# Power_3_3V.net
KiCad netlist of a schematic drawn in Altium Designer
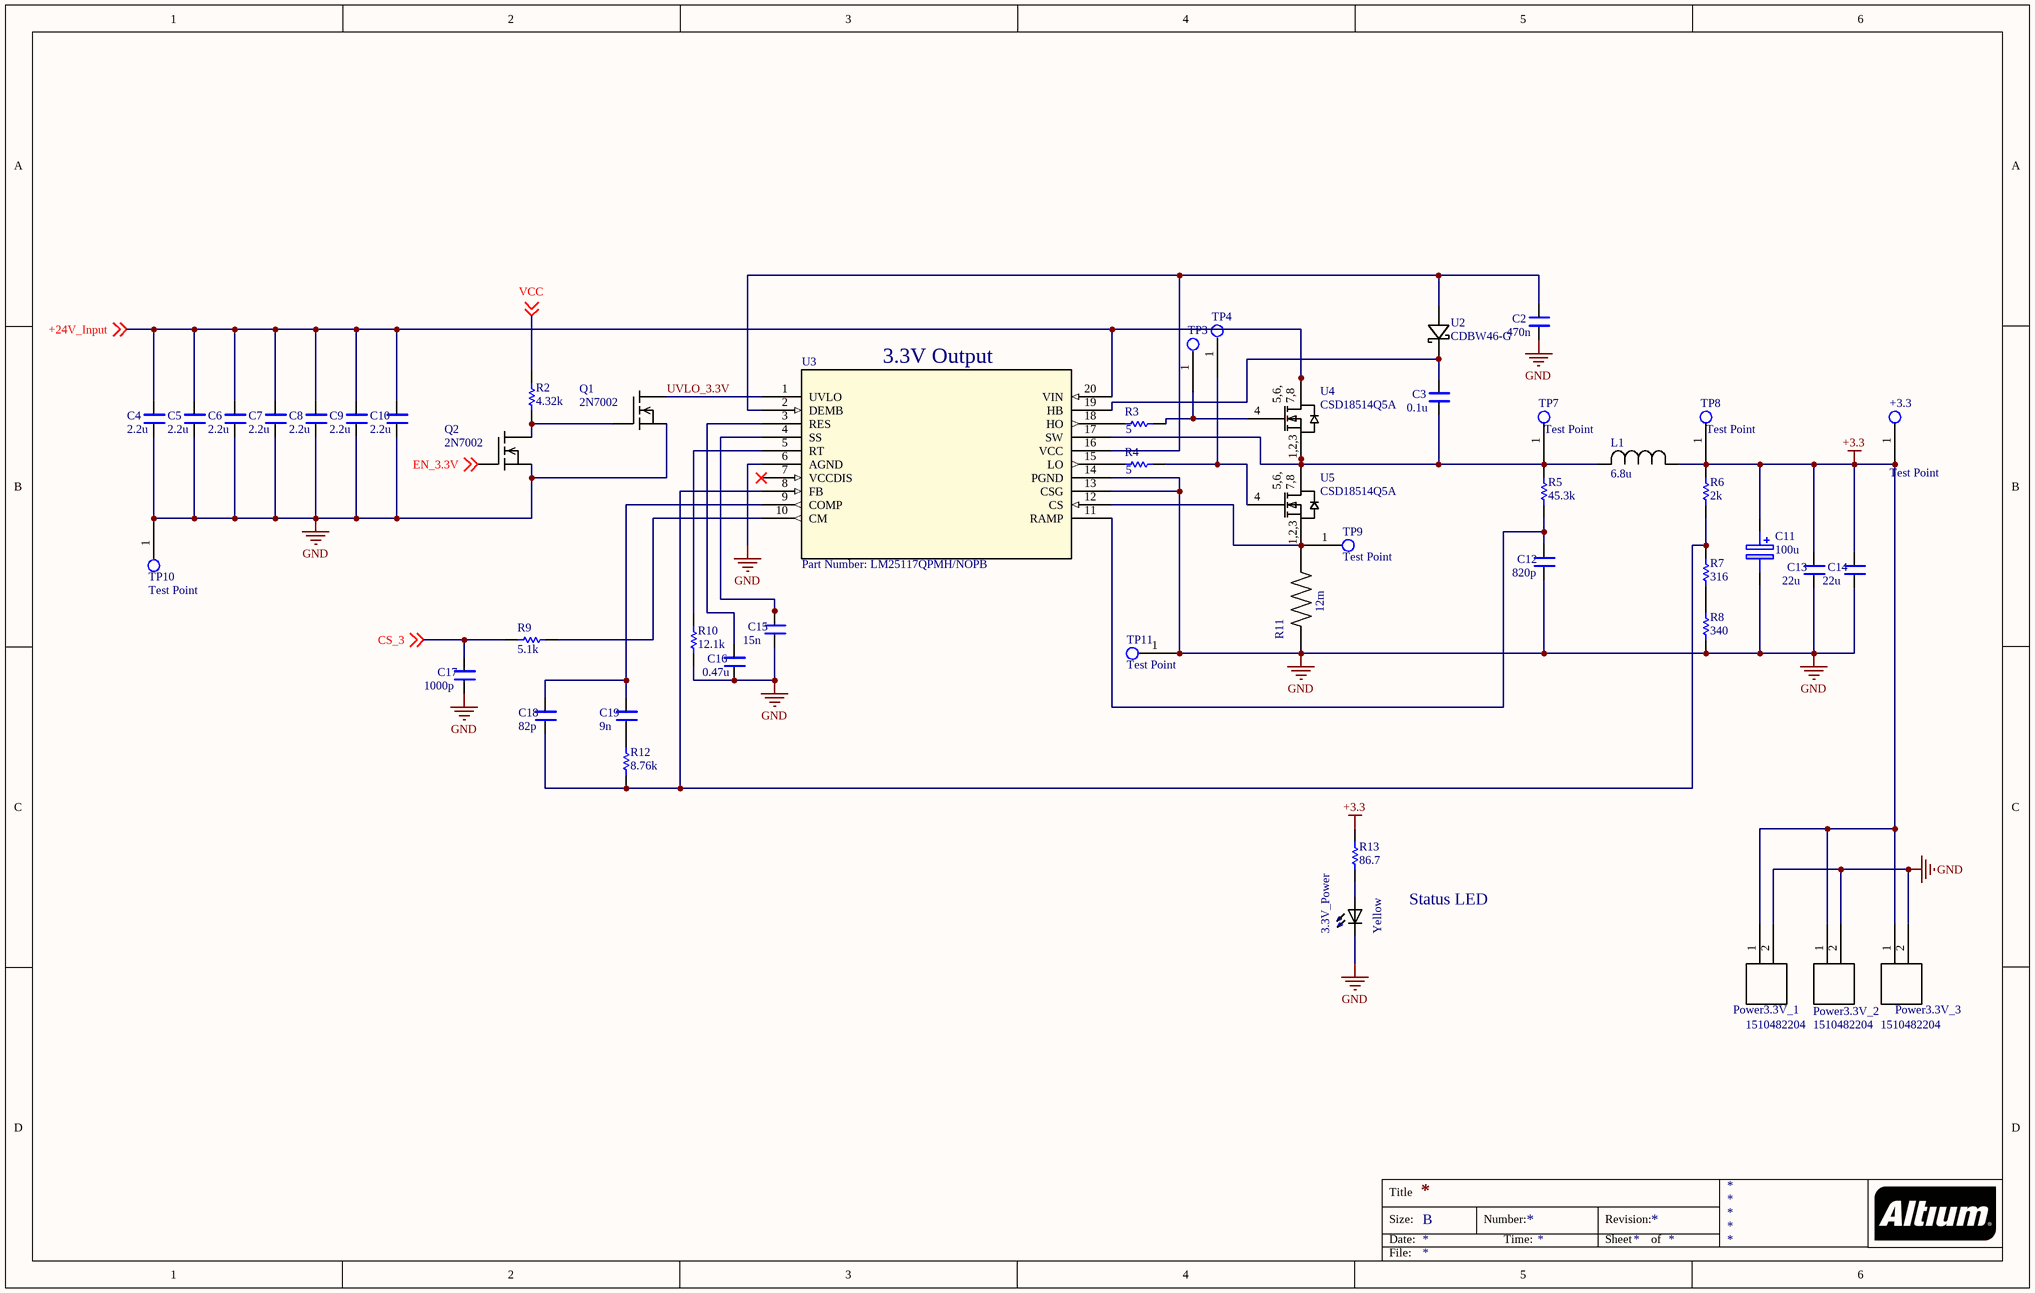
[diagram p0: Power_3.3V.SchDoc]

(export (version "E")
  (design (tool "Eeschema 10.0.6"))
  (components
    (comp (ref "+3.3")
      (value "Test Point")
      (footprint "Test Point Through-hole")
      (libsource (lib "Test Points") (part "Test Point"))
    )
    (comp (ref "3.3V_Power")
      (value "Yellow")
      (footprint "*DIOC200X125X110_LTST-C171KSKT(Primary)")
      (description "Yellow 2 x 1.25 x 0.8 mm 130Â° Water Clear 50 mcd 2 V LED SMT")
      (fields (field (name "MP") "LTST-C171KSKT") (field (name "DIGI-KEY_PART_NUMBER") "160-1428-1-ND"))
      (libsource (lib "LTST-C171KSKT") (part "LTST-C171KSKT"))
    )
    (comp (ref "C2")
      (value "470n")
      (footprint "*CAPC2012X88N")
      (description "100pF Â±5% 250V Ceramic Capacitor C0G, NP0 0805 _2012 Metric_")
      (fields (field (name "MF") "KEMET") (field (name "DIGI-KEY_PART_NUMBER") "399-15000-1-ND"))
      (libsource (lib "C0805C101JAGAC7800") (part "C0805C101JAGAC7800"))
    )
    (comp (ref "C3")
      (value "0.1u")
      (footprint "*CAPC2012X88N")
      (description "100pF Â±5% 250V Ceramic Capacitor C0G, NP0 0805 _2012 Metric_")
      (fields (field (name "MF") "KEMET") (field (name "DIGI-KEY_PART_NUMBER") "399-15000-1-ND"))
      (libsource (lib "C0805C101JAGAC7800") (part "C0805C101JAGAC7800"))
    )
    (comp (ref "C4")
      (value "2.2u")
      (footprint "*CAPC2012X88N")
      (description "100pF Â±5% 250V Ceramic Capacitor C0G, NP0 0805 _2012 Metric_")
      (fields (field (name "MF") "KEMET") (field (name "DIGI-KEY_PART_NUMBER") "399-15000-1-ND"))
      (libsource (lib "C0805C101JAGAC7800") (part "C0805C101JAGAC7800"))
    )
    (comp (ref "C5")
      (value "2.2u")
      (footprint "*CAPC2012X88N")
      (description "100pF Â±5% 250V Ceramic Capacitor C0G, NP0 0805 _2012 Metric_")
      (fields (field (name "MF") "KEMET") (field (name "DIGI-KEY_PART_NUMBER") "399-15000-1-ND"))
      (libsource (lib "C0805C101JAGAC7800") (part "C0805C101JAGAC7800"))
    )
    (comp (ref "C6")
      (value "2.2u")
      (footprint "*CAPC2012X88N")
      (description "100pF Â±5% 250V Ceramic Capacitor C0G, NP0 0805 _2012 Metric_")
      (fields (field (name "MF") "KEMET") (field (name "DIGI-KEY_PART_NUMBER") "399-15000-1-ND"))
      (libsource (lib "C0805C101JAGAC7800") (part "C0805C101JAGAC7800"))
    )
    (comp (ref "C7")
      (value "2.2u")
      (footprint "*CAPC2012X88N")
      (description "100pF Â±5% 250V Ceramic Capacitor C0G, NP0 0805 _2012 Metric_")
      (fields (field (name "MF") "KEMET") (field (name "DIGI-KEY_PART_NUMBER") "399-15000-1-ND"))
      (libsource (lib "C0805C101JAGAC7800") (part "C0805C101JAGAC7800"))
    )
    (comp (ref "C8")
      (value "2.2u")
      (footprint "*CAPC2012X88N")
      (description "100pF Â±5% 250V Ceramic Capacitor C0G, NP0 0805 _2012 Metric_")
      (fields (field (name "MF") "KEMET") (field (name "DIGI-KEY_PART_NUMBER") "399-15000-1-ND"))
      (libsource (lib "C0805C101JAGAC7800") (part "C0805C101JAGAC7800"))
    )
    (comp (ref "C9")
      (value "2.2u")
      (footprint "*CAPC2012X88N")
      (description "100pF Â±5% 250V Ceramic Capacitor C0G, NP0 0805 _2012 Metric_")
      (fields (field (name "MF") "KEMET") (field (name "DIGI-KEY_PART_NUMBER") "399-15000-1-ND"))
      (libsource (lib "C0805C101JAGAC7800") (part "C0805C101JAGAC7800"))
    )
    (comp (ref "C10")
      (value "2.2u")
      (footprint "*CAPC2012X88N")
      (description "100pF Â±5% 250V Ceramic Capacitor C0G, NP0 0805 _2012 Metric_")
      (fields (field (name "MF") "KEMET") (field (name "DIGI-KEY_PART_NUMBER") "399-15000-1-ND"))
      (libsource (lib "C0805C101JAGAC7800") (part "C0805C101JAGAC7800"))
    )
    (comp (ref "C11")
      (value "100u")
      (footprint "CAPPRD500W65D1000H1800")
      (fields
        (field (name "MANUFACTURER_PART_NUMBER") "EEUFC1V331")
        (field (name "RS PART NUMBER") "1081337")
      )
      (libsource (lib "Power Distribution") (part "EEUFC1V331"))
    )
    (comp (ref "C12")
      (value "820p")
      (footprint "*CAPC2012X88N")
      (description "100pF Â±5% 250V Ceramic Capacitor C0G, NP0 0805 _2012 Metric_")
      (fields (field (name "MF") "KEMET") (field (name "DIGI-KEY_PART_NUMBER") "399-15000-1-ND"))
      (libsource (lib "C0805C101JAGAC7800") (part "C0805C101JAGAC7800"))
    )
    (comp (ref "C13")
      (value "22u")
      (footprint "*CAPC2012X88N")
      (description "100pF Â±5% 250V Ceramic Capacitor C0G, NP0 0805 _2012 Metric_")
      (fields (field (name "MF") "KEMET") (field (name "DIGI-KEY_PART_NUMBER") "399-15000-1-ND"))
      (libsource (lib "C0805C101JAGAC7800") (part "C0805C101JAGAC7800"))
    )
    (comp (ref "C14")
      (value "22u")
      (footprint "*CAPC2012X88N")
      (description "100pF Â±5% 250V Ceramic Capacitor C0G, NP0 0805 _2012 Metric_")
      (fields (field (name "MF") "KEMET") (field (name "DIGI-KEY_PART_NUMBER") "399-15000-1-ND"))
      (libsource (lib "C0805C101JAGAC7800") (part "C0805C101JAGAC7800"))
    )
    (comp (ref "C15")
      (value "15n")
      (footprint "*CAPC2012X88N")
      (description "100pF Â±5% 250V Ceramic Capacitor C0G, NP0 0805 _2012 Metric_")
      (fields (field (name "MF") "KEMET") (field (name "DIGI-KEY_PART_NUMBER") "399-15000-1-ND"))
      (libsource (lib "C0805C101JAGAC7800") (part "C0805C101JAGAC7800"))
    )
    (comp (ref "C16")
      (value "0.47u")
      (footprint "*CAPC2012X88N")
      (description "100pF Â±5% 250V Ceramic Capacitor C0G, NP0 0805 _2012 Metric_")
      (fields (field (name "MF") "KEMET") (field (name "DIGI-KEY_PART_NUMBER") "399-15000-1-ND"))
      (libsource (lib "C0805C101JAGAC7800") (part "C0805C101JAGAC7800"))
    )
    (comp (ref "C17")
      (value "1000p")
      (footprint "*CAPC2012X88N")
      (description "100pF Â±5% 250V Ceramic Capacitor C0G, NP0 0805 _2012 Metric_")
      (fields (field (name "MF") "KEMET") (field (name "DIGI-KEY_PART_NUMBER") "399-15000-1-ND"))
      (libsource (lib "C0805C101JAGAC7800") (part "C0805C101JAGAC7800"))
    )
    (comp (ref "C18")
      (value "82p")
      (footprint "*CAPC2012X88N")
      (description "100pF Â±5% 250V Ceramic Capacitor C0G, NP0 0805 _2012 Metric_")
      (fields (field (name "MF") "KEMET") (field (name "DIGI-KEY_PART_NUMBER") "399-15000-1-ND"))
      (libsource (lib "C0805C101JAGAC7800") (part "C0805C101JAGAC7800"))
    )
    (comp (ref "C19")
      (value "9n")
      (footprint "*CAPC2012X88N")
      (description "100pF Â±5% 250V Ceramic Capacitor C0G, NP0 0805 _2012 Metric_")
      (fields (field (name "MF") "KEMET") (field (name "DIGI-KEY_PART_NUMBER") "399-15000-1-ND"))
      (libsource (lib "C0805C101JAGAC7800") (part "C0805C101JAGAC7800"))
    )
    (comp (ref "L1")
      (value "6.8u")
      (footprint "IND_BOURNS_SRP12")
      (description "No Description Available")
      (fields
        (field (name "MANUFACTURER_PART_NUMBER") "SRP1270-6R8M")
        (field (name "COPYRIGHT") "Copyright (C) 2018 Accelerated Designs. All rights reserved")
      )
      (libsource (lib "Inductor") (part "SRP1270-6R8M"))
    )
    (comp (ref "Power3.3V_1")
      (value "1510482204")
      (footprint "1510482204")
      (description "Molex 6.5MM 2 pin connector, used for power connections. P/N 1510482204 and similar models.")
      (libsource (lib "Power Distribution") (part "1510482204"))
    )
    (comp (ref "Power3.3V_2")
      (value "1510482204")
      (footprint "1510482204")
      (description "Molex 6.5MM 2 pin connector, used for power connections. P/N 1510482204 and similar models.")
      (libsource (lib "Power Distribution") (part "1510482204"))
    )
    (comp (ref "Power3.3V_3")
      (value "1510482204")
      (footprint "1510482204")
      (description "Molex 6.5MM 2 pin connector, used for power connections. P/N 1510482204 and similar models.")
      (libsource (lib "Power Distribution") (part "1510482204"))
    )
    (comp (ref "Q1")
      (value "2N7002")
      (footprint "*SOT23")
      (description "Trans MOSFET N-CH 60V 0.115A 3-Pin SOT-23 T/R")
      (fields (field (name "MF") "ON Semiconductor"))
      (libsource (lib "2N7002") (part "2N7002"))
    )
    (comp (ref "Q2")
      (value "2N7002")
      (footprint "*SOT23")
      (description "Trans MOSFET N-CH 60V 0.115A 3-Pin SOT-23 T/R")
      (fields (field (name "MF") "ON Semiconductor"))
      (libsource (lib "2N7002") (part "2N7002"))
    )
    (comp (ref "R2")
      (value "4.32k")
      (footprint "RESC0805(2012)_M")
      (description "8M06 0.125W 1% 0805 (2012 Metric)  SMD")
      (fields (field (name "POWER") "0.125 W") (field (name "TOLERANCE") "1 %"))
      (libsource (lib "Altium Content Vault") (part "RES"))
    )
    (comp (ref "R3")
      (value "5")
      (footprint "AXIAL-0.3")
      (description "120R 0.125W 5% 0805 (2012 Metric)  SMD")
      (fields (field (name "TOLERANCE") "5 %") (field (name "POWER") "0.125 W"))
      (libsource (lib "Power Distribution") (part "120R 5% 0805"))
    )
    (comp (ref "R4")
      (value "5")
      (footprint "AXIAL-0.3")
      (description "120R 0.125W 5% 0805 (2012 Metric)  SMD")
      (fields (field (name "TOLERANCE") "5 %") (field (name "POWER") "0.125 W"))
      (libsource (lib "Power Distribution") (part "120R 5% 0805"))
    )
    (comp (ref "R5")
      (value "45.3k")
      (footprint "RESC0805(2012)_M")
      (description "8M06 0.125W 1% 0805 (2012 Metric)  SMD")
      (fields (field (name "POWER") "0.125 W") (field (name "TOLERANCE") "1 %"))
      (libsource (lib "Altium Content Vault") (part "RES"))
    )
    (comp (ref "R6")
      (value "2k")
      (footprint "RESC0805(2012)_M")
      (description "8M06 0.125W 1% 0805 (2012 Metric)  SMD")
      (fields (field (name "POWER") "0.125 W") (field (name "TOLERANCE") "1 %"))
      (libsource (lib "Altium Content Vault") (part "RES"))
    )
    (comp (ref "R7")
      (value "316")
      (footprint "RESC0805(2012)_M")
      (description "8M06 0.125W 1% 0805 (2012 Metric)  SMD")
      (fields (field (name "POWER") "0.125 W") (field (name "TOLERANCE") "1 %"))
      (libsource (lib "Altium Content Vault") (part "RES"))
    )
    (comp (ref "R8")
      (value "340")
      (footprint "RESC0805(2012)_M")
      (description "8M06 0.125W 1% 0805 (2012 Metric)  SMD")
      (fields (field (name "POWER") "0.125 W") (field (name "TOLERANCE") "1 %"))
      (libsource (lib "Altium Content Vault") (part "RES"))
    )
    (comp (ref "R9")
      (value "5.1k")
      (footprint "RESC0805(2012)_M")
      (description "8M06 0.125W 1% 0805 (2012 Metric)  SMD")
      (fields (field (name "POWER") "0.125 W") (field (name "TOLERANCE") "1 %"))
      (libsource (lib "Altium Content Vault") (part "RES"))
    )
    (comp (ref "R10")
      (value "12.1k")
      (footprint "RESC0805(2012)_M")
      (description "8M06 0.125W 1% 0805 (2012 Metric)  SMD")
      (fields (field (name "POWER") "0.125 W") (field (name "TOLERANCE") "1 %"))
      (libsource (lib "Altium Content Vault") (part "RES"))
    )
    (comp (ref "R11")
      (value "12m")
      (footprint "*RESC6432X110N")
      (description "Res Thick Film 2512 0.012 Ohm 1% 1W Pad SMD Automotive T/R")
      (fields (field (name "MP") "ERJ-M1WSF12MU") (field (name "DIGI-KEY_PART_NUMBER") "P12MCT-ND"))
      (libsource (lib "ERJ-M1WSF12MU") (part "ERJ-M1WSF12MU"))
    )
    (comp (ref "R12")
      (value "8.76k")
      (footprint "RESC0805(2012)_M")
      (description "8M06 0.125W 1% 0805 (2012 Metric)  SMD")
      (fields (field (name "POWER") "0.125 W") (field (name "TOLERANCE") "1 %"))
      (libsource (lib "Altium Content Vault") (part "RES"))
    )
    (comp (ref "R13")
      (value "86.7")
      (footprint "RESC0805(2012)_M")
      (description "8M06 0.125W 1% 0805 (2012 Metric)  SMD")
      (fields (field (name "POWER") "0.125 W") (field (name "TOLERANCE") "1 %"))
      (libsource (lib "Altium Content Vault") (part "RES"))
    )
    (comp (ref "TP3")
      (value "~")
      (footprint "Test Point Through-hole")
      (libsource (lib "Test Points") (part "Test Point"))
    )
    (comp (ref "TP4")
      (value "~")
      (footprint "Test Point Through-hole")
      (libsource (lib "Test Points") (part "Test Point"))
    )
    (comp (ref "TP7")
      (value "Test Point")
      (footprint "Test Point Through-hole")
      (libsource (lib "Test Points") (part "Test Point"))
    )
    (comp (ref "TP8")
      (value "Test Point")
      (footprint "Test Point Through-hole")
      (libsource (lib "Test Points") (part "Test Point"))
    )
    (comp (ref "TP9")
      (value "Test Point")
      (footprint "Test Point Through-hole")
      (libsource (lib "Test Points") (part "Test Point"))
    )
    (comp (ref "TP10")
      (value "Test Point")
      (footprint "Test Point Through-hole")
      (libsource (lib "Test Points") (part "Test Point"))
    )
    (comp (ref "TP11")
      (value "Test Point")
      (footprint "Test Point Through-hole")
      (libsource (lib "Test Points") (part "Test Point"))
    )
    (comp (ref "U2")
      (value "CDBW46-G")
      (footprint "CDBW")
      (description "No Description Available")
      (fields (field (name "COPYRIGHT") "Copyright (C) 2018 Accelerated Designs. All rights reserved"))
      (libsource (lib "DIODE SCHOTTKY 100V 150MA") (part "CDBW46-G"))
    )
    (comp (ref "U3")
      (value "Part Number: LM25117QPMH/NOPB")
      (footprint "MXA20A")
      (description "No Description Available")
      (fields
        (field (name "MANUFACTURER") "Texas Instruments")
        (field (name "MANUFACTURER_PART_NUMBER") "LM25117QPMH/NOPB")
        (field (name "COPYRIGHT") "Copyright (C) 2018 Accelerated Designs. All rights reserved")
      )
      (libsource (lib "2019-11-16_22-35-15") (part "LM25117QPMH/NOPB"))
    )
    (comp (ref "U4")
      (value "CSD18514Q5A")
      (footprint "DQJ0008A")
      (description "No Description Available")
      (fields (field (name "COPYRIGHT") "Copyright (C) 2018 Accelerated Designs. All rights reserved"))
      (libsource (lib "ul_CSD18514Q5A") (part "CSD18514Q5A"))
    )
    (comp (ref "U5")
      (value "CSD18514Q5A")
      (footprint "DQJ0008A")
      (description "No Description Available")
      (fields (field (name "COPYRIGHT") "Copyright (C) 2018 Accelerated Designs. All rights reserved"))
      (libsource (lib "ul_CSD18514Q5A") (part "CSD18514Q5A"))
    )
  )
  (nets
    (net (code "1") (name "+3.3") (class "Default")
      (node (ref "+3.3") (pin "1") (pinfunction "1_1") (pintype "passive"))
      (node (ref "C11") (pin "1") (pinfunction "+_1") (pintype "passive"))
      (node (ref "C13") (pin "2") (pinfunction "2_2") (pintype "passive"))
      (node (ref "C14") (pin "2") (pinfunction "2_2") (pintype "passive"))
      (node (ref "L1") (pin "1") (pinfunction "1_1") (pintype "passive"))
      (node (ref "Power3.3V_1") (pin "1") (pintype "passive"))
      (node (ref "Power3.3V_2") (pin "1") (pintype "passive"))
      (node (ref "Power3.3V_3") (pin "1") (pintype "passive"))
      (node (ref "R13") (pin "2") (pinfunction "2_2") (pintype "passive"))
      (node (ref "R6") (pin "2") (pinfunction "2_2") (pintype "passive"))
      (node (ref "TP8") (pin "1") (pinfunction "1_1") (pintype "passive"))
    )
    (net (code "2") (name "+24V_Input") (class "Default")
      (node (ref "C10") (pin "2") (pinfunction "2_2") (pintype "passive"))
      (node (ref "C4") (pin "2") (pinfunction "2_2") (pintype "passive"))
      (node (ref "C5") (pin "2") (pinfunction "2_2") (pintype "passive"))
      (node (ref "C6") (pin "2") (pinfunction "2_2") (pintype "passive"))
      (node (ref "C7") (pin "2") (pinfunction "2_2") (pintype "passive"))
      (node (ref "C8") (pin "2") (pinfunction "2_2") (pintype "passive"))
      (node (ref "C9") (pin "2") (pinfunction "2_2") (pintype "passive"))
      (node (ref "U3") (pin "20") (pinfunction "VIN_20") (pintype "input"))
      (node (ref "U4") (pin "5") (pinfunction "D_5") (pintype "passive"))
      (node (ref "U4") (pin "6") (pinfunction "D_6") (pintype "passive"))
      (node (ref "U4") (pin "7") (pinfunction "D_7") (pintype "passive"))
      (node (ref "U4") (pin "8") (pinfunction "D_8") (pintype "passive"))
    )
    (net (code "3") (name "/UVLO_3.3V") (class "Default")
      (node (ref "Q1") (pin "3") (pinfunction "D_3") (pintype "passive"))
      (node (ref "U3") (pin "1") (pinfunction "UVLO_1") (pintype "passive"))
    )
    (net (code "4") (name "CS_3") (class "Default")
      (node (ref "C17") (pin "2") (pinfunction "2_2") (pintype "passive"))
      (node (ref "R9") (pin "2") (pinfunction "2_2") (pintype "passive"))
    )
    (net (code "5") (name "EN_3.3V") (class "Default")
      (node (ref "Q2") (pin "1") (pinfunction "G_1") (pintype "passive"))
    )
    (net (code "6") (name "GND") (class "Default")
      (node (ref "3.3V_Power") (pin "NEG") (pinfunction "NEG_NEG") (pintype "passive"))
      (node (ref "C10") (pin "1") (pinfunction "1_1") (pintype "passive"))
      (node (ref "C11") (pin "2") (pinfunction "-_2") (pintype "passive"))
      (node (ref "C12") (pin "1") (pinfunction "1_1") (pintype "passive"))
      (node (ref "C13") (pin "1") (pinfunction "1_1") (pintype "passive"))
      (node (ref "C14") (pin "1") (pinfunction "1_1") (pintype "passive"))
      (node (ref "C15") (pin "1") (pinfunction "1_1") (pintype "passive"))
      (node (ref "C16") (pin "1") (pinfunction "1_1") (pintype "passive"))
      (node (ref "C17") (pin "1") (pinfunction "1_1") (pintype "passive"))
      (node (ref "C2") (pin "1") (pinfunction "1_1") (pintype "passive"))
      (node (ref "C4") (pin "1") (pinfunction "1_1") (pintype "passive"))
      (node (ref "C5") (pin "1") (pinfunction "1_1") (pintype "passive"))
      (node (ref "C6") (pin "1") (pinfunction "1_1") (pintype "passive"))
      (node (ref "C7") (pin "1") (pinfunction "1_1") (pintype "passive"))
      (node (ref "C8") (pin "1") (pinfunction "1_1") (pintype "passive"))
      (node (ref "C9") (pin "1") (pinfunction "1_1") (pintype "passive"))
      (node (ref "Power3.3V_1") (pin "2") (pintype "passive"))
      (node (ref "Power3.3V_2") (pin "2") (pintype "passive"))
      (node (ref "Power3.3V_3") (pin "2") (pintype "passive"))
      (node (ref "Q1") (pin "2") (pinfunction "S_2") (pintype "passive"))
      (node (ref "Q2") (pin "2") (pinfunction "S_2") (pintype "passive"))
      (node (ref "R10") (pin "1") (pinfunction "1_1") (pintype "passive"))
      (node (ref "R11") (pin "1") (pinfunction "1_1") (pintype "passive"))
      (node (ref "R8") (pin "1") (pinfunction "1_1") (pintype "passive"))
      (node (ref "TP10") (pin "1") (pinfunction "1_1") (pintype "passive"))
      (node (ref "TP11") (pin "1") (pinfunction "1_1") (pintype "passive"))
      (node (ref "U3") (pin "13") (pinfunction "CSG_13") (pintype "passive"))
      (node (ref "U3") (pin "14") (pinfunction "PGND_14") (pintype "power_in"))
      (node (ref "U3") (pin "6") (pinfunction "AGND_6") (pintype "power_in"))
    )
    (net (code "7") (name "Net-(3.3V_Power-PadPOS)") (class "Default")
      (node (ref "3.3V_Power") (pin "POS") (pinfunction "POS_POS") (pintype "passive"))
      (node (ref "R13") (pin "1") (pinfunction "1_1") (pintype "passive"))
    )
    (net (code "8") (name "Net-(C19-Pad1)") (class "Default")
      (node (ref "C19") (pin "1") (pinfunction "1_1") (pintype "passive"))
      (node (ref "R12") (pin "2") (pinfunction "2_2") (pintype "passive"))
    )
    (net (code "9") (name "Net-(Q1-G)") (class "Default")
      (node (ref "Q1") (pin "1") (pinfunction "G_1") (pintype "passive"))
      (node (ref "Q2") (pin "3") (pinfunction "D_3") (pintype "passive"))
      (node (ref "R2") (pin "1") (pinfunction "1_1") (pintype "passive"))
    )
    (net (code "10") (name "Net-(R7-Pad1)") (class "Default")
      (node (ref "R7") (pin "1") (pinfunction "1_1") (pintype "passive"))
      (node (ref "R8") (pin "2") (pinfunction "2_2") (pintype "passive"))
    )
    (net (code "11") (name "Net-(U3-CM)") (class "Default")
      (node (ref "R9") (pin "1") (pinfunction "1_1") (pintype "passive"))
      (node (ref "U3") (pin "10") (pinfunction "CM_10") (pintype "output"))
    )
    (net (code "12") (name "Net-(U3-COMP)") (class "Default")
      (node (ref "C18") (pin "2") (pinfunction "2_2") (pintype "passive"))
      (node (ref "C19") (pin "2") (pinfunction "2_2") (pintype "passive"))
      (node (ref "U3") (pin "9") (pinfunction "COMP_9") (pintype "output"))
    )
    (net (code "13") (name "Net-(U3-CS)") (class "Default")
      (node (ref "R11") (pin "2") (pinfunction "2_2") (pintype "passive"))
      (node (ref "TP9") (pin "1") (pinfunction "1_1") (pintype "passive"))
      (node (ref "U3") (pin "12") (pinfunction "CS_12") (pintype "input"))
      (node (ref "U5") (pin "1") (pinfunction "S_1") (pintype "passive"))
      (node (ref "U5") (pin "2") (pinfunction "S_2") (pintype "passive"))
      (node (ref "U5") (pin "3") (pinfunction "S_3") (pintype "passive"))
    )
    (net (code "14") (name "Net-(U3-DEMB)") (class "Default")
      (node (ref "C2") (pin "2") (pinfunction "2_2") (pintype "passive"))
      (node (ref "U2") (pin "2") (pinfunction "2_2") (pintype "passive"))
      (node (ref "U3") (pin "16") (pinfunction "VCC_16") (pintype "power_in"))
      (node (ref "U3") (pin "2") (pinfunction "DEMB_2") (pintype "input"))
    )
    (net (code "15") (name "Net-(U3-FB)") (class "Default")
      (node (ref "C18") (pin "1") (pinfunction "1_1") (pintype "passive"))
      (node (ref "R12") (pin "1") (pinfunction "1_1") (pintype "passive"))
      (node (ref "R6") (pin "1") (pinfunction "1_1") (pintype "passive"))
      (node (ref "R7") (pin "2") (pinfunction "2_2") (pintype "passive"))
      (node (ref "U3") (pin "8") (pinfunction "FB_8") (pintype "input"))
    )
    (net (code "16") (name "Net-(U3-HB)") (class "Default")
      (node (ref "C3") (pin "2") (pinfunction "2_2") (pintype "passive"))
      (node (ref "U2") (pin "1") (pinfunction "1_1") (pintype "passive"))
      (node (ref "U3") (pin "19") (pinfunction "HB_19") (pintype "passive"))
    )
    (net (code "17") (name "Net-(U3-HO)") (class "Default")
      (node (ref "R3") (pin "1") (pinfunction "1_1") (pintype "passive"))
      (node (ref "U3") (pin "18") (pinfunction "HO_18") (pintype "output"))
    )
    (net (code "18") (name "Net-(U3-LO)") (class "Default")
      (node (ref "R4") (pin "1") (pinfunction "1_1") (pintype "passive"))
      (node (ref "U3") (pin "15") (pinfunction "LO_15") (pintype "output"))
    )
    (net (code "19") (name "Net-(U3-RAMP)") (class "Default")
      (node (ref "C12") (pin "2") (pinfunction "2_2") (pintype "passive"))
      (node (ref "R5") (pin "1") (pinfunction "1_1") (pintype "passive"))
      (node (ref "U3") (pin "11") (pinfunction "RAMP_11") (pintype "passive"))
    )
    (net (code "20") (name "Net-(U3-RES)") (class "Default")
      (node (ref "C16") (pin "2") (pinfunction "2_2") (pintype "passive"))
      (node (ref "U3") (pin "3") (pinfunction "RES_3") (pintype "passive"))
    )
    (net (code "21") (name "Net-(U3-RT)") (class "Default")
      (node (ref "R10") (pin "2") (pinfunction "2_2") (pintype "passive"))
      (node (ref "U3") (pin "5") (pinfunction "RT_5") (pintype "passive"))
    )
    (net (code "22") (name "Net-(U3-SS)") (class "Default")
      (node (ref "C15") (pin "2") (pinfunction "2_2") (pintype "passive"))
      (node (ref "U3") (pin "4") (pinfunction "SS_4") (pintype "passive"))
    )
    (net (code "23") (name "Net-(U3-SW)") (class "Default")
      (node (ref "C3") (pin "1") (pinfunction "1_1") (pintype "passive"))
      (node (ref "L1") (pin "2") (pinfunction "2_2") (pintype "passive"))
      (node (ref "R5") (pin "2") (pinfunction "2_2") (pintype "passive"))
      (node (ref "TP7") (pin "1") (pinfunction "1_1") (pintype "passive"))
      (node (ref "U3") (pin "17") (pinfunction "SW_17") (pintype "passive"))
      (node (ref "U4") (pin "1") (pinfunction "S_1") (pintype "passive"))
      (node (ref "U4") (pin "2") (pinfunction "S_2") (pintype "passive"))
      (node (ref "U4") (pin "3") (pinfunction "S_3") (pintype "passive"))
      (node (ref "U5") (pin "5") (pinfunction "D_5") (pintype "passive"))
      (node (ref "U5") (pin "6") (pinfunction "D_6") (pintype "passive"))
      (node (ref "U5") (pin "7") (pinfunction "D_7") (pintype "passive"))
      (node (ref "U5") (pin "8") (pinfunction "D_8") (pintype "passive"))
    )
    (net (code "24") (name "Net-(U4-G)") (class "Default")
      (node (ref "R3") (pin "2") (pinfunction "2_2") (pintype "passive"))
      (node (ref "TP3") (pin "1") (pinfunction "1_1") (pintype "passive"))
      (node (ref "U4") (pin "4") (pinfunction "G_4") (pintype "passive"))
    )
    (net (code "25") (name "Net-(U5-G)") (class "Default")
      (node (ref "R4") (pin "2") (pinfunction "2_2") (pintype "passive"))
      (node (ref "TP4") (pin "1") (pinfunction "1_1") (pintype "passive"))
      (node (ref "U5") (pin "4") (pinfunction "G_4") (pintype "passive"))
    )
    (net (code "26") (name "VCC") (class "Default")
      (node (ref "R2") (pin "2") (pinfunction "2_2") (pintype "passive"))
    )
    (net (code "27") (name "unconnected-(U3-VCCDIS-Pad7)") (class "Default")
      (node (ref "U3") (pin "7") (pinfunction "VCCDIS_7") (pintype "input+no_connect"))
    )
  )
)
